# dwatch.net
KiCad netlist of a schematic drawn in Altium Designer
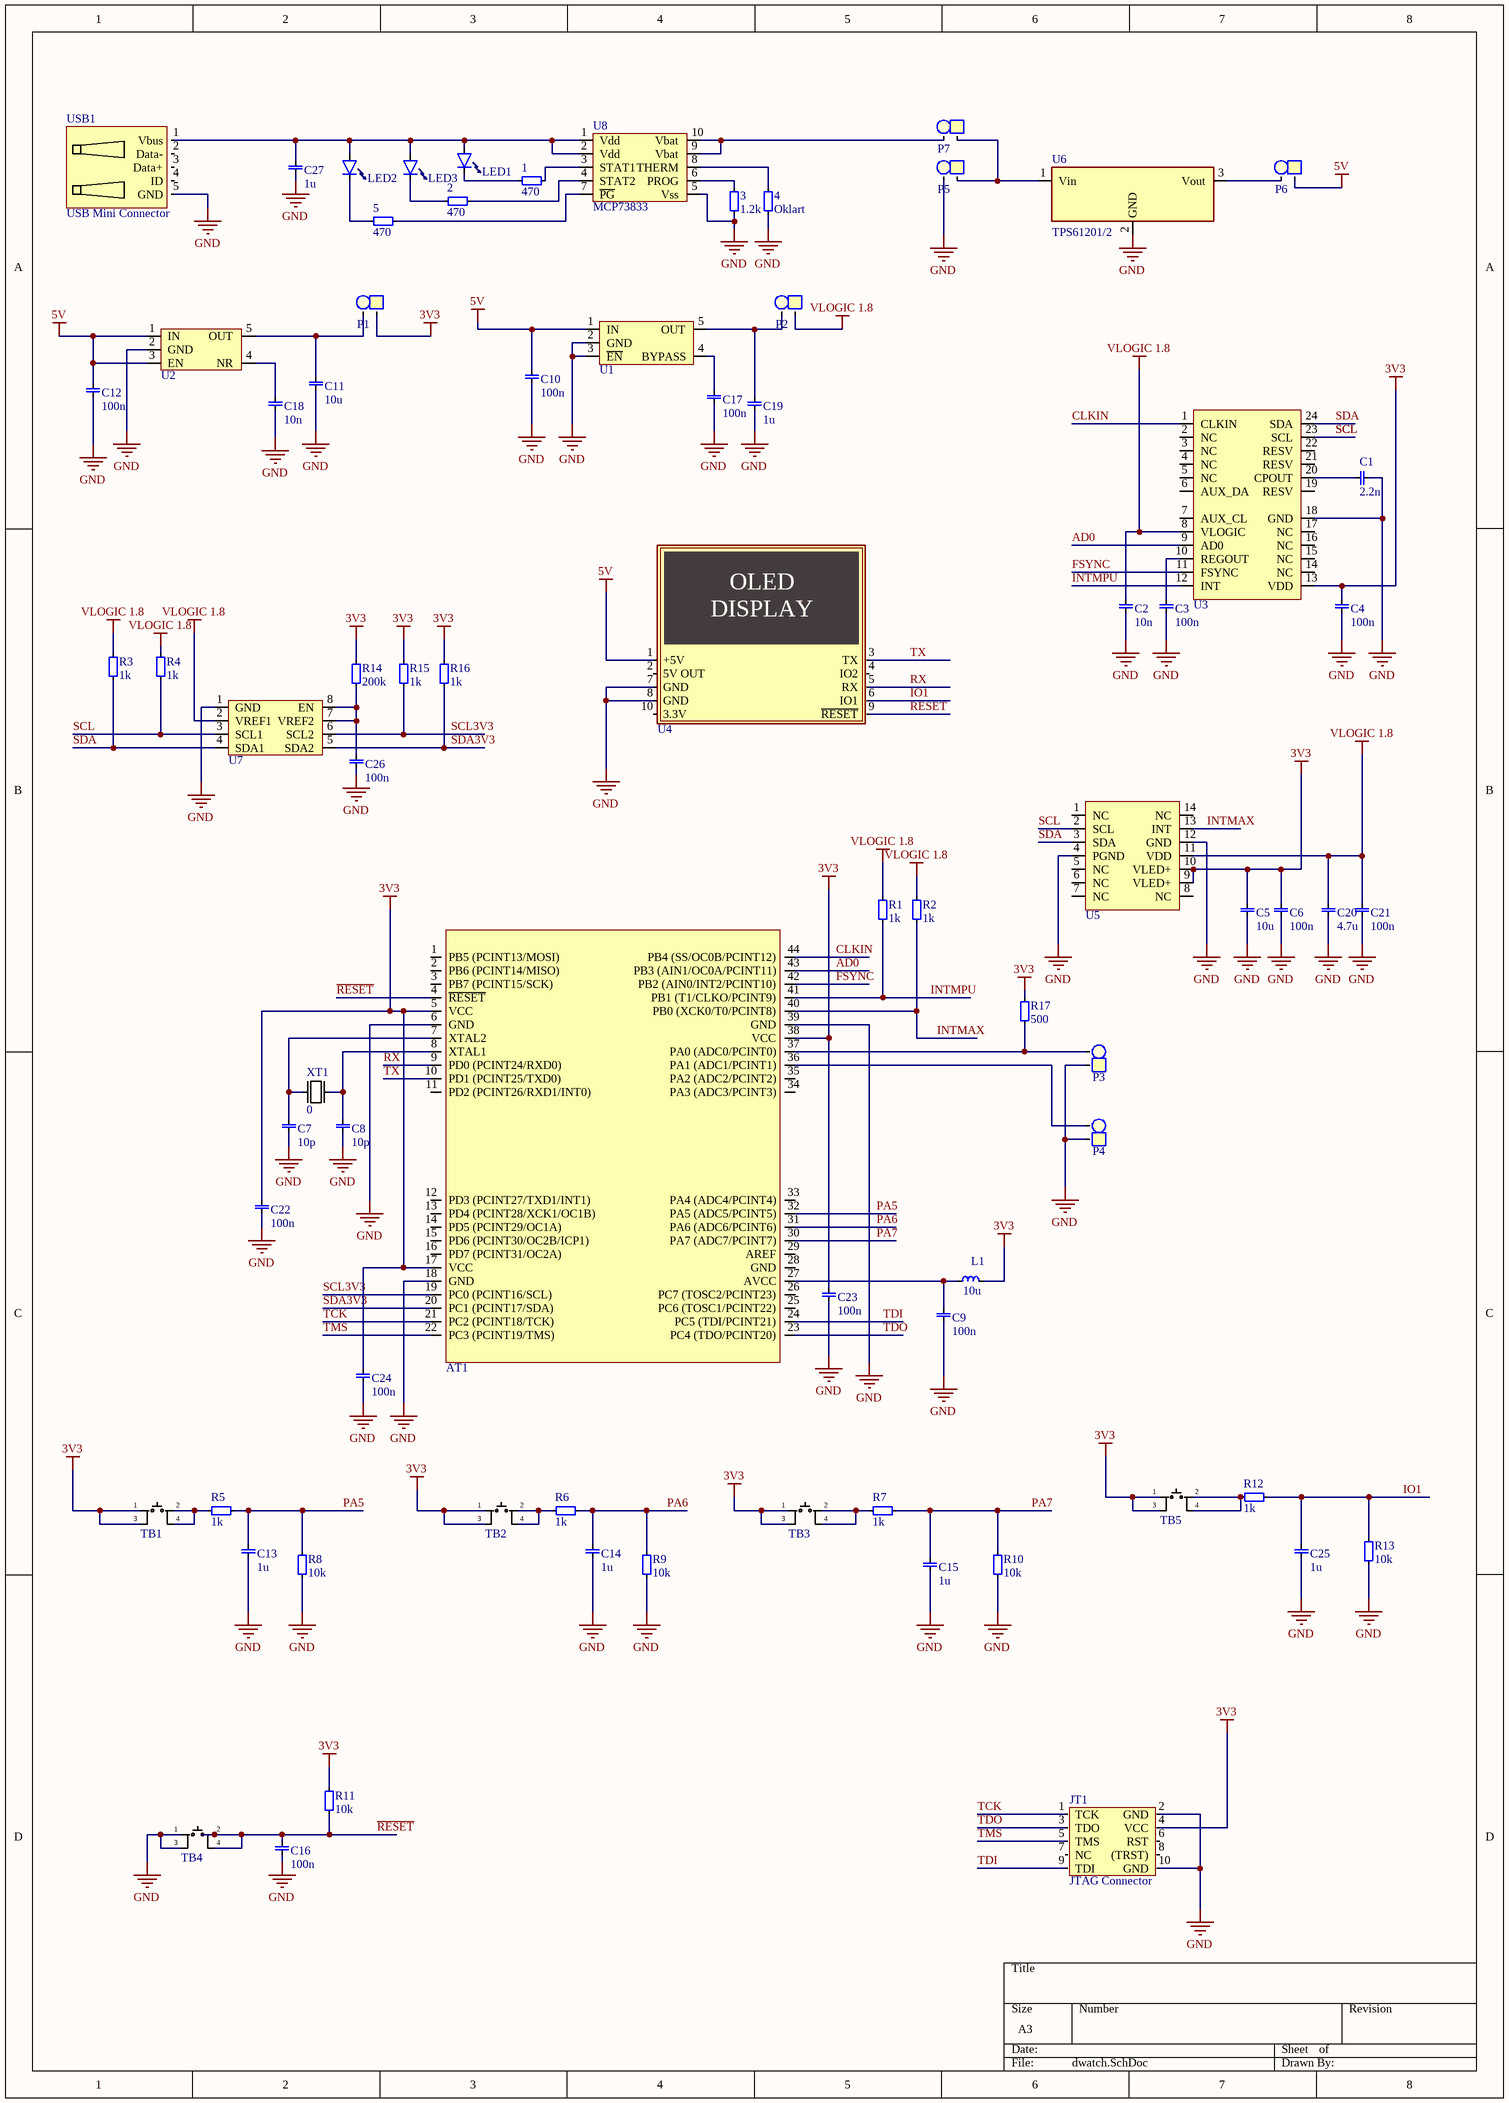
[diagram p0: dwatch.SchDoc]

(export (version "E")
  (design (tool "Eeschema 10.0.6"))
  (components
    (comp (ref "1")
      (value "470")
      (footprint "1206")
      (description "Resistor")
      (fields (field (name "Comment") "1206, resistor"))
      (libsource (lib "eitp15_lab1_lib") (part "1206, resistor"))
    )
    (comp (ref "2")
      (value "470")
      (footprint "1206")
      (description "Resistor")
      (fields (field (name "Comment") "1206, resistor"))
      (libsource (lib "eitp15_lab1_lib") (part "1206, resistor"))
    )
    (comp (ref "3")
      (value "1.2k")
      (footprint "1206")
      (description "Resistor")
      (fields (field (name "Comment") "1206, resistor"))
      (libsource (lib "eitp15_lab1_lib") (part "1206, resistor"))
    )
    (comp (ref "4")
      (value "Oklart")
      (footprint "1206")
      (description "Resistor")
      (fields (field (name "Comment") "1206, resistor"))
      (libsource (lib "eitp15_lab1_lib") (part "1206, resistor"))
    )
    (comp (ref "5")
      (value "470")
      (footprint "1206")
      (description "Resistor")
      (fields (field (name "Comment") "1206, resistor"))
      (libsource (lib "eitp15_lab1_lib") (part "1206, resistor"))
    )
    (comp (ref "AT1")
      (value "ATmega644PA")
      (footprint "TQFP-44")
      (description "ATmega644PA - Small but big and PicoPower")
      (libsource (lib "eitp15_lab1_lib") (part "ATmega644PA"))
    )
    (comp (ref "C1")
      (value "2.2n")
      (footprint "1206, capasitor")
      (fields (field (name "Comment") "1206, capacitor"))
      (libsource (lib "eitp15_lab1_lib") (part "1206, capacitor"))
    )
    (comp (ref "C2")
      (value "10n")
      (footprint "1206, capasitor")
      (fields (field (name "Comment") "1206, capacitor"))
      (libsource (lib "eitp15_lab1_lib") (part "1206, capacitor"))
    )
    (comp (ref "C3")
      (value "100n")
      (footprint "1206, capasitor")
      (fields (field (name "Comment") "1206, capacitor"))
      (libsource (lib "eitp15_lab1_lib") (part "1206, capacitor"))
    )
    (comp (ref "C4")
      (value "100n")
      (footprint "1206, capasitor")
      (fields (field (name "Comment") "1206, capacitor"))
      (libsource (lib "eitp15_lab1_lib") (part "1206, capacitor"))
    )
    (comp (ref "C5")
      (value "10u")
      (footprint "1206, capasitor")
      (fields (field (name "Comment") "1206, capacitor"))
      (libsource (lib "eitp15_lab1_lib") (part "1206, capacitor"))
    )
    (comp (ref "C6")
      (value "100n")
      (footprint "1206, capasitor")
      (fields (field (name "Comment") "1206, capacitor"))
      (libsource (lib "eitp15_lab1_lib") (part "1206, capacitor"))
    )
    (comp (ref "C7")
      (value "10p")
      (footprint "1206, capasitor")
      (fields (field (name "Comment") "1206, capacitor"))
      (libsource (lib "eitp15_lab1_lib") (part "1206, capacitor"))
    )
    (comp (ref "C8")
      (value "10p")
      (footprint "1206, capasitor")
      (fields (field (name "Comment") "1206, capacitor"))
      (libsource (lib "eitp15_lab1_lib") (part "1206, capacitor"))
    )
    (comp (ref "C9")
      (value "100n")
      (footprint "1206, capasitor")
      (fields (field (name "Comment") "1206, capacitor"))
      (libsource (lib "eitp15_lab1_lib") (part "1206, capacitor"))
    )
    (comp (ref "C10")
      (value "100n")
      (footprint "1206, capasitor")
      (fields (field (name "Comment") "1206, capacitor"))
      (libsource (lib "eitp15_lab1_lib") (part "1206, capacitor"))
    )
    (comp (ref "C11")
      (value "10u")
      (footprint "1206, capasitor")
      (fields (field (name "Comment") "1206, capacitor"))
      (libsource (lib "eitp15_lab1_lib") (part "1206, capacitor"))
    )
    (comp (ref "C12")
      (value "100n")
      (footprint "1206, capasitor")
      (fields (field (name "Comment") "1206, capacitor"))
      (libsource (lib "eitp15_lab1_lib") (part "1206, capacitor"))
    )
    (comp (ref "C13")
      (value "1u")
      (footprint "1206, capasitor")
      (fields (field (name "Comment") "1206, capacitor"))
      (libsource (lib "eitp15_lab1_lib") (part "1206, capacitor"))
    )
    (comp (ref "C14")
      (value "1u")
      (footprint "1206, capasitor")
      (fields (field (name "Comment") "1206, capacitor"))
      (libsource (lib "eitp15_lab1_lib") (part "1206, capacitor"))
    )
    (comp (ref "C15")
      (value "1u")
      (footprint "1206, capasitor")
      (fields (field (name "Comment") "1206, capacitor"))
      (libsource (lib "eitp15_lab1_lib") (part "1206, capacitor"))
    )
    (comp (ref "C16")
      (value "100n")
      (footprint "1206, capasitor")
      (fields (field (name "Comment") "1206, capacitor"))
      (libsource (lib "eitp15_lab1_lib") (part "1206, capacitor"))
    )
    (comp (ref "C17")
      (value "100n")
      (footprint "1206, capasitor")
      (fields (field (name "Comment") "1206, capacitor"))
      (libsource (lib "eitp15_lab1_lib") (part "1206, capacitor"))
    )
    (comp (ref "C18")
      (value "10n")
      (footprint "1206, capasitor")
      (fields (field (name "Comment") "1206, capacitor"))
      (libsource (lib "eitp15_lab1_lib") (part "1206, capacitor"))
    )
    (comp (ref "C19")
      (value "1u")
      (footprint "1206, capasitor")
      (fields (field (name "Comment") "1206, capacitor"))
      (libsource (lib "eitp15_lab1_lib") (part "1206, capacitor"))
    )
    (comp (ref "C20")
      (value "4.7u")
      (footprint "1206, capasitor")
      (fields (field (name "Comment") "1206, capacitor"))
      (libsource (lib "eitp15_lab1_lib") (part "1206, capacitor"))
    )
    (comp (ref "C21")
      (value "100n")
      (footprint "1206, capasitor")
      (fields (field (name "Comment") "1206, capacitor"))
      (libsource (lib "eitp15_lab1_lib") (part "1206, capacitor"))
    )
    (comp (ref "C22")
      (value "100n")
      (footprint "1206, capasitor")
      (fields (field (name "Comment") "1206, capacitor"))
      (libsource (lib "eitp15_lab1_lib") (part "1206, capacitor"))
    )
    (comp (ref "C23")
      (value "100n")
      (footprint "1206, capasitor")
      (fields (field (name "Comment") "1206, capacitor"))
      (libsource (lib "eitp15_lab1_lib") (part "1206, capacitor"))
    )
    (comp (ref "C24")
      (value "100n")
      (footprint "1206, capasitor")
      (fields (field (name "Comment") "1206, capacitor"))
      (libsource (lib "eitp15_lab1_lib") (part "1206, capacitor"))
    )
    (comp (ref "C25")
      (value "1u")
      (footprint "1206, capasitor")
      (fields (field (name "Comment") "1206, capacitor"))
      (libsource (lib "eitp15_lab1_lib") (part "1206, capacitor"))
    )
    (comp (ref "C26")
      (value "100n")
      (footprint "1206, capasitor")
      (fields (field (name "Comment") "1206, capacitor"))
      (libsource (lib "eitp15_lab1_lib") (part "1206, capacitor"))
    )
    (comp (ref "C27")
      (value "1u")
      (footprint "1206, capasitor")
      (fields (field (name "Comment") "1206, capacitor"))
      (libsource (lib "eitp15_lab1_lib") (part "1206, capacitor"))
    )
    (comp (ref "JT1")
      (value "JTAG Connector")
      (footprint "Atmel_JTAG")
      (description "Atmel JTAG Connector")
      (libsource (lib "eitp15_lab1_lib") (part "Atmel JTAG"))
    )
    (comp (ref "L1")
      (value "10u")
      (footprint "1812, coil")
      (fields (field (name "Comment") "Coil"))
      (libsource (lib "eitp15_lab1_lib") (part "Coil"))
    )
    (comp (ref "LED1")
      (value "0805, LED")
      (footprint "0805_led")
      (libsource (lib "eitp15_lab1_lib") (part "0805, LED"))
    )
    (comp (ref "LED2")
      (value "0805, LED")
      (footprint "0805_led")
      (libsource (lib "eitp15_lab1_lib") (part "0805, LED"))
    )
    (comp (ref "LED3")
      (value "0805, LED")
      (footprint "0805_led")
      (libsource (lib "eitp15_lab1_lib") (part "0805, LED"))
    )
    (comp (ref "P1")
      (value "1x2 Pin Header")
      (footprint "1x2HEADER")
      (description "2.54 mm, TH")
      (libsource (lib "") (part "1x2 Pin Header_1"))
    )
    (comp (ref "P2")
      (value "1x2 Pin Header")
      (footprint "1x2HEADER")
      (description "2.54 mm, TH")
      (libsource (lib "") (part "1x2 Pin Header_1"))
    )
    (comp (ref "P3")
      (value "1x2 Pin Header")
      (footprint "1x2HEADER")
      (description "2.54 mm, TH")
      (libsource (lib "eitp15_lab1_lib") (part "1x2 Pin Header"))
    )
    (comp (ref "P4")
      (value "1x2 Pin Header")
      (footprint "1x2HEADER")
      (description "2.54 mm, TH")
      (libsource (lib "eitp15_lab1_lib") (part "1x2 Pin Header"))
    )
    (comp (ref "P5")
      (value "1x2 Pin Header")
      (footprint "1x2HEADER")
      (description "2.54 mm, TH")
      (libsource (lib "") (part "1x2 Pin Header_1"))
    )
    (comp (ref "P6")
      (value "1x2 Pin Header")
      (footprint "1x2HEADER")
      (description "2.54 mm, TH")
      (libsource (lib "") (part "1x2 Pin Header_1"))
    )
    (comp (ref "P7")
      (value "1x2 Pin Header")
      (footprint "1x2HEADER")
      (description "2.54 mm, TH")
      (libsource (lib "") (part "1x2 Pin Header_1"))
    )
    (comp (ref "R1")
      (value "1k")
      (footprint "1206")
      (description "Resistor")
      (fields (field (name "Comment") "1206, resistor"))
      (libsource (lib "eitp15_lab1_lib") (part "1206, resistor"))
    )
    (comp (ref "R2")
      (value "1k")
      (footprint "1206")
      (description "Resistor")
      (fields (field (name "Comment") "1206, resistor"))
      (libsource (lib "eitp15_lab1_lib") (part "1206, resistor"))
    )
    (comp (ref "R3")
      (value "1k")
      (footprint "1206")
      (description "Resistor")
      (fields (field (name "Comment") "1206, resistor"))
      (libsource (lib "eitp15_lab1_lib") (part "1206, resistor"))
    )
    (comp (ref "R4")
      (value "1k")
      (footprint "1206")
      (description "Resistor")
      (fields (field (name "Comment") "1206, resistor"))
      (libsource (lib "eitp15_lab1_lib") (part "1206, resistor"))
    )
    (comp (ref "R5")
      (value "1k")
      (footprint "1206")
      (description "Resistor")
      (fields (field (name "Comment") "1206, resistor"))
      (libsource (lib "eitp15_lab1_lib") (part "1206, resistor"))
    )
    (comp (ref "R6")
      (value "1k")
      (footprint "1206")
      (description "Resistor")
      (fields (field (name "Comment") "1206, resistor"))
      (libsource (lib "eitp15_lab1_lib") (part "1206, resistor"))
    )
    (comp (ref "R7")
      (value "1k")
      (footprint "1206")
      (description "Resistor")
      (fields (field (name "Comment") "1206, resistor"))
      (libsource (lib "eitp15_lab1_lib") (part "1206, resistor"))
    )
    (comp (ref "R8")
      (value "10k")
      (footprint "1206")
      (description "Resistor")
      (fields (field (name "Comment") "1206, resistor"))
      (libsource (lib "eitp15_lab1_lib") (part "1206, resistor"))
    )
    (comp (ref "R9")
      (value "10k")
      (footprint "1206")
      (description "Resistor")
      (fields (field (name "Comment") "1206, resistor"))
      (libsource (lib "eitp15_lab1_lib") (part "1206, resistor"))
    )
    (comp (ref "R10")
      (value "10k")
      (footprint "1206")
      (description "Resistor")
      (fields (field (name "Comment") "1206, resistor"))
      (libsource (lib "eitp15_lab1_lib") (part "1206, resistor"))
    )
    (comp (ref "R11")
      (value "10k")
      (footprint "1206")
      (description "Resistor")
      (fields (field (name "Comment") "1206, resistor"))
      (libsource (lib "eitp15_lab1_lib") (part "1206, resistor"))
    )
    (comp (ref "R12")
      (value "1k")
      (footprint "1206")
      (description "Resistor")
      (fields (field (name "Comment") "1206, resistor"))
      (libsource (lib "eitp15_lab1_lib") (part "1206, resistor"))
    )
    (comp (ref "R13")
      (value "10k")
      (footprint "1206")
      (description "Resistor")
      (fields (field (name "Comment") "1206, resistor"))
      (libsource (lib "eitp15_lab1_lib") (part "1206, resistor"))
    )
    (comp (ref "R14")
      (value "200k")
      (footprint "1206")
      (description "Resistor")
      (fields (field (name "Comment") "1206, resistor"))
      (libsource (lib "eitp15_lab1_lib") (part "1206, resistor"))
    )
    (comp (ref "R15")
      (value "1k")
      (footprint "1206")
      (description "Resistor")
      (fields (field (name "Comment") "1206, resistor"))
      (libsource (lib "eitp15_lab1_lib") (part "1206, resistor"))
    )
    (comp (ref "R16")
      (value "1k")
      (footprint "1206")
      (description "Resistor")
      (fields (field (name "Comment") "1206, resistor"))
      (libsource (lib "eitp15_lab1_lib") (part "1206, resistor"))
    )
    (comp (ref "R17")
      (value "500")
      (footprint "1206")
      (description "Resistor")
      (fields (field (name "Comment") "1206, resistor"))
      (libsource (lib "eitp15_lab1_lib") (part "1206, resistor"))
    )
    (comp (ref "TB1")
      (value "Tactile Button")
      (footprint "Button smd")
      (description "Tactile Switch Small Low")
      (libsource (lib "eitp15_lab1_lib") (part "Button SMD"))
    )
    (comp (ref "TB2")
      (value "Tactile Button")
      (footprint "Button smd")
      (description "Tactile Switch Small Low")
      (libsource (lib "eitp15_lab1_lib") (part "Button SMD"))
    )
    (comp (ref "TB3")
      (value "Tactile Button")
      (footprint "Button smd")
      (description "Tactile Switch Small Low")
      (libsource (lib "eitp15_lab1_lib") (part "Button SMD"))
    )
    (comp (ref "TB4")
      (value "Tactile Button")
      (footprint "Button smd")
      (description "Tactile Switch Small Low")
      (libsource (lib "eitp15_lab1_lib") (part "Button SMD"))
    )
    (comp (ref "TB5")
      (value "Tactile Button")
      (footprint "Button smd")
      (description "Tactile Switch Small Low")
      (libsource (lib "eitp15_lab1_lib") (part "Button SMD"))
    )
    (comp (ref "U1")
      (value "TPS79118DBVR")
      (footprint "SOT23-5")
      (libsource (lib "dwatch") (part "TPS79118DBVR"))
    )
    (comp (ref "U2")
      (value "TPS79333DBVRG4")
      (footprint "SOT23-5")
      (libsource (lib "dwatch") (part "TPS79333DBVRG4"))
    )
    (comp (ref "U3")
      (value "MPU-6050")
      (footprint "MPU6050_QNF24")
      (libsource (lib "dwatch") (part "MPU-6050"))
    )
    (comp (ref "U4")
      (value "uOLED-128G2")
      (footprint "uOLED-128G2")
      (libsource (lib "jclib") (part "uOLED-128G2"))
    )
    (comp (ref "U5")
      (value "MAX30101")
      (footprint "MAX30101EFD")
      (libsource (lib "dwatch") (part "MAX30101"))
    )
    (comp (ref "U6")
      (value "TPS61201/2")
      (footprint "tps61201_2")
      (libsource (lib "tps61201_2_lib") (part "TPS61201/2"))
    )
    (comp (ref "U7") (value "PCA9306") (footprint "PCA9306") (libsource (lib "dwatch") (part "PCA9306")))
    (comp (ref "U8") (value "MCP73833") (footprint "MCP73833") (libsource (lib "dwatch") (part "MCP73833")))
    (comp (ref "USB1")
      (value "USB Mini Connector")
      (footprint "USB Mini TH")
      (libsource (lib "jclib") (part "USB Mini Connector"))
    )
    (comp (ref "XT1")
      (value "0")
      (footprint "XTAL_SMD_LP")
      (description "16 MHz, SMD, 5mm x 3,2mm, 30 ppm")
      (fields (field (name "Comment") "XTAL TXC 7A"))
      (libsource (lib "eitp15_lab1_lib") (part "XTAL TXC 7A"))
    )
  )
  (nets
    (net (code "1") (name "/AD0") (class "Default")
      (node (ref "AT1") (pin "43") (pinfunction "PB3_(AIN1/OC0A/PCINT11)_43") (pintype "passive"))
      (node (ref "U3") (pin "9") (pinfunction "AD0_9") (pintype "passive"))
    )
    (net (code "2") (name "/CLKIN") (class "Default")
      (node (ref "AT1") (pin "44") (pinfunction "PB4_(SS/OC0B/PCINT12)_44") (pintype "passive"))
      (node (ref "U3") (pin "1") (pinfunction "CLKIN_1") (pintype "passive"))
    )
    (net (code "3") (name "/FSYNC") (class "Default")
      (node (ref "AT1") (pin "42") (pinfunction "PB2_(AIN0/INT2/PCINT10)_42") (pintype "passive"))
      (node (ref "U3") (pin "11") (pinfunction "FSYNC_11") (pintype "passive"))
    )
    (net (code "4") (name "/INTMAX") (class "Default")
      (node (ref "AT1") (pin "40") (pinfunction "PB0_(XCK0/T0/PCINT8)_40") (pintype "passive"))
      (node (ref "R2") (pin "1") (pinfunction "1_1") (pintype "passive"))
      (node (ref "U5") (pin "13") (pinfunction "INT_13") (pintype "passive"))
    )
    (net (code "5") (name "/INTMPU") (class "Default")
      (node (ref "AT1") (pin "41") (pinfunction "PB1_(T1/CLKO/PCINT9)_41") (pintype "passive"))
      (node (ref "R1") (pin "1") (pinfunction "1_1") (pintype "passive"))
      (node (ref "U3") (pin "12") (pinfunction "INT_12") (pintype "passive"))
    )
    (net (code "6") (name "/IO1") (class "Default")
      (node (ref "C25") (pin "1") (pinfunction "1_1") (pintype "passive"))
      (node (ref "R12") (pin "0") (pinfunction "0_0") (pintype "passive"))
      (node (ref "R13") (pin "0") (pinfunction "0_0") (pintype "passive"))
      (node (ref "U4") (pin "6") (pinfunction "IO1_6") (pintype "passive"))
    )
    (net (code "7") (name "/PA5") (class "Default")
      (node (ref "AT1") (pin "32") (pinfunction "PA5_(ADC5/PCINT5)_32") (pintype "passive"))
      (node (ref "C13") (pin "1") (pinfunction "1_1") (pintype "passive"))
      (node (ref "R5") (pin "0") (pinfunction "0_0") (pintype "passive"))
      (node (ref "R8") (pin "0") (pinfunction "0_0") (pintype "passive"))
    )
    (net (code "8") (name "/PA6") (class "Default")
      (node (ref "AT1") (pin "31") (pinfunction "PA6_(ADC6/PCINT6)_31") (pintype "passive"))
      (node (ref "C14") (pin "1") (pinfunction "1_1") (pintype "passive"))
      (node (ref "R6") (pin "0") (pinfunction "0_0") (pintype "passive"))
      (node (ref "R9") (pin "0") (pinfunction "0_0") (pintype "passive"))
    )
    (net (code "9") (name "/PA7") (class "Default")
      (node (ref "AT1") (pin "30") (pinfunction "PA7_(ADC7/PCINT7)_30") (pintype "passive"))
      (node (ref "C15") (pin "1") (pinfunction "1_1") (pintype "passive"))
      (node (ref "R10") (pin "0") (pinfunction "0_0") (pintype "passive"))
      (node (ref "R7") (pin "0") (pinfunction "0_0") (pintype "passive"))
    )
    (net (code "10") (name "/RX") (class "Default")
      (node (ref "AT1") (pin "9") (pinfunction "PD0_(PCINT24/RXD0)_9") (pintype "passive"))
      (node (ref "U4") (pin "5") (pinfunction "RX_5") (pintype "passive"))
    )
    (net (code "11") (name "/SCL") (class "Default")
      (node (ref "R4") (pin "1") (pinfunction "1_1") (pintype "passive"))
      (node (ref "U3") (pin "23") (pinfunction "SCL_23") (pintype "passive"))
      (node (ref "U5") (pin "2") (pinfunction "SCL_2") (pintype "passive"))
      (node (ref "U7") (pin "3") (pinfunction "SCL1_3") (pintype "passive"))
    )
    (net (code "12") (name "/SCL3V3") (class "Default")
      (node (ref "AT1") (pin "19") (pinfunction "PC0_(PCINT16/SCL)_19") (pintype "passive"))
      (node (ref "R15") (pin "1") (pinfunction "1_1") (pintype "passive"))
      (node (ref "U7") (pin "6") (pinfunction "SCL2_6") (pintype "passive"))
    )
    (net (code "13") (name "/SDA") (class "Default")
      (node (ref "R3") (pin "1") (pinfunction "1_1") (pintype "passive"))
      (node (ref "U3") (pin "24") (pinfunction "SDA_24") (pintype "passive"))
      (node (ref "U5") (pin "3") (pinfunction "SDA_3") (pintype "passive"))
      (node (ref "U7") (pin "4") (pinfunction "SDA1_4") (pintype "passive"))
    )
    (net (code "14") (name "/SDA3V3") (class "Default")
      (node (ref "AT1") (pin "20") (pinfunction "PC1_(PCINT17/SDA)_20") (pintype "passive"))
      (node (ref "R16") (pin "1") (pinfunction "1_1") (pintype "passive"))
      (node (ref "U7") (pin "5") (pinfunction "SDA2_5") (pintype "passive"))
    )
    (net (code "15") (name "/TCK") (class "Default")
      (node (ref "AT1") (pin "21") (pinfunction "PC2_(PCINT18/TCK)_21") (pintype "passive"))
      (node (ref "JT1") (pin "1") (pinfunction "TCK_1") (pintype "passive"))
    )
    (net (code "16") (name "/TDI") (class "Default")
      (node (ref "AT1") (pin "24") (pinfunction "PC5_(TDI/PCINT21)_24") (pintype "passive"))
      (node (ref "JT1") (pin "9") (pinfunction "TDI_9") (pintype "passive"))
    )
    (net (code "17") (name "/TDO") (class "Default")
      (node (ref "AT1") (pin "23") (pinfunction "PC4_(TDO/PCINT20)_23") (pintype "passive"))
      (node (ref "JT1") (pin "3") (pinfunction "TDO_3") (pintype "passive"))
    )
    (net (code "18") (name "/TMS") (class "Default")
      (node (ref "AT1") (pin "22") (pinfunction "PC3_(PCINT19/TMS)_22") (pintype "passive"))
      (node (ref "JT1") (pin "5") (pinfunction "TMS_5") (pintype "passive"))
    )
    (net (code "19") (name "/TX") (class "Default")
      (node (ref "AT1") (pin "10") (pinfunction "PD1_(PCINT25/TXD0)_10") (pintype "passive"))
      (node (ref "U4") (pin "3") (pinfunction "TX_3") (pintype "passive"))
    )
    (net (code "20") (name "/~{RESET}") (class "Default")
      (node (ref "AT1") (pin "4") (pinfunction "~{RESET}_4") (pintype "passive"))
      (node (ref "C16") (pin "1") (pinfunction "1_1") (pintype "passive"))
      (node (ref "R11") (pin "1") (pinfunction "1_1") (pintype "passive"))
      (node (ref "TB4") (pin "2") (pinfunction "2_2") (pintype "passive"))
      (node (ref "TB4") (pin "4") (pinfunction "4_4") (pintype "passive"))
      (node (ref "U4") (pin "9") (pinfunction "~{RESET}_9") (pintype "passive"))
    )
    (net (code "21") (name "3V3") (class "Default")
      (node (ref "AT1") (pin "17") (pinfunction "VCC_17") (pintype "passive"))
      (node (ref "AT1") (pin "38") (pinfunction "VCC_38") (pintype "passive"))
      (node (ref "AT1") (pin "5") (pinfunction "VCC_5") (pintype "passive"))
      (node (ref "C22") (pin "1") (pinfunction "1_1") (pintype "passive"))
      (node (ref "C23") (pin "1") (pinfunction "1_1") (pintype "passive"))
      (node (ref "C24") (pin "1") (pinfunction "1_1") (pintype "passive"))
      (node (ref "C4") (pin "1") (pinfunction "1_1") (pintype "passive"))
      (node (ref "C5") (pin "1") (pinfunction "1_1") (pintype "passive"))
      (node (ref "C6") (pin "1") (pinfunction "1_1") (pintype "passive"))
      (node (ref "JT1") (pin "4") (pinfunction "VCC_4") (pintype "passive"))
      (node (ref "L1") (pin "1") (pinfunction "1_1") (pintype "passive"))
      (node (ref "P1") (pin "1") (pinfunction "1_1") (pintype "passive"))
      (node (ref "R11") (pin "0") (pinfunction "0_0") (pintype "passive"))
      (node (ref "R14") (pin "0") (pinfunction "0_0") (pintype "passive"))
      (node (ref "R15") (pin "0") (pinfunction "0_0") (pintype "passive"))
      (node (ref "R16") (pin "0") (pinfunction "0_0") (pintype "passive"))
      (node (ref "R17") (pin "0") (pinfunction "0_0") (pintype "passive"))
      (node (ref "TB1") (pin "1") (pinfunction "1_1") (pintype "passive"))
      (node (ref "TB1") (pin "3") (pinfunction "3_3") (pintype "passive"))
      (node (ref "TB2") (pin "1") (pinfunction "1_1") (pintype "passive"))
      (node (ref "TB2") (pin "3") (pinfunction "3_3") (pintype "passive"))
      (node (ref "TB3") (pin "1") (pinfunction "1_1") (pintype "passive"))
      (node (ref "TB3") (pin "3") (pinfunction "3_3") (pintype "passive"))
      (node (ref "TB5") (pin "1") (pinfunction "1_1") (pintype "passive"))
      (node (ref "TB5") (pin "3") (pinfunction "3_3") (pintype "passive"))
      (node (ref "U3") (pin "13") (pinfunction "VDD_13") (pintype "passive"))
      (node (ref "U5") (pin "10") (pinfunction "VLED+_10") (pintype "passive"))
      (node (ref "U5") (pin "9") (pinfunction "VLED+_9") (pintype "passive"))
    )
    (net (code "22") (name "5V") (class "Default")
      (node (ref "C10") (pin "1") (pinfunction "1_1") (pintype "passive"))
      (node (ref "C12") (pin "1") (pinfunction "1_1") (pintype "passive"))
      (node (ref "P6") (pin "1") (pinfunction "1_1") (pintype "passive"))
      (node (ref "U1") (pin "1") (pinfunction "IN_1") (pintype "passive"))
      (node (ref "U2") (pin "1") (pinfunction "IN_1") (pintype "passive"))
      (node (ref "U2") (pin "3") (pinfunction "EN_3") (pintype "passive"))
      (node (ref "U4") (pin "1") (pinfunction "+5V_1") (pintype "passive"))
    )
    (net (code "23") (name "GND") (class "Default")
      (node (ref "3") (pin "1") (pinfunction "1_1") (pintype "passive"))
      (node (ref "4") (pin "1") (pinfunction "1_1") (pintype "passive"))
      (node (ref "AT1") (pin "18") (pinfunction "GND_18") (pintype "passive"))
      (node (ref "AT1") (pin "39") (pinfunction "GND_39") (pintype "passive"))
      (node (ref "AT1") (pin "6") (pinfunction "GND_6") (pintype "passive"))
      (node (ref "C1") (pin "1") (pinfunction "1_1") (pintype "passive"))
      (node (ref "C10") (pin "0") (pinfunction "0_0") (pintype "passive"))
      (node (ref "C11") (pin "0") (pinfunction "0_0") (pintype "passive"))
      (node (ref "C12") (pin "0") (pinfunction "0_0") (pintype "passive"))
      (node (ref "C13") (pin "0") (pinfunction "0_0") (pintype "passive"))
      (node (ref "C14") (pin "0") (pinfunction "0_0") (pintype "passive"))
      (node (ref "C15") (pin "0") (pinfunction "0_0") (pintype "passive"))
      (node (ref "C16") (pin "0") (pinfunction "0_0") (pintype "passive"))
      (node (ref "C17") (pin "0") (pinfunction "0_0") (pintype "passive"))
      (node (ref "C18") (pin "0") (pinfunction "0_0") (pintype "passive"))
      (node (ref "C19") (pin "0") (pinfunction "0_0") (pintype "passive"))
      (node (ref "C2") (pin "0") (pinfunction "0_0") (pintype "passive"))
      (node (ref "C20") (pin "0") (pinfunction "0_0") (pintype "passive"))
      (node (ref "C21") (pin "0") (pinfunction "0_0") (pintype "passive"))
      (node (ref "C22") (pin "0") (pinfunction "0_0") (pintype "passive"))
      (node (ref "C23") (pin "0") (pinfunction "0_0") (pintype "passive"))
      (node (ref "C24") (pin "0") (pinfunction "0_0") (pintype "passive"))
      (node (ref "C25") (pin "0") (pinfunction "0_0") (pintype "passive"))
      (node (ref "C26") (pin "0") (pinfunction "0_0") (pintype "passive"))
      (node (ref "C27") (pin "0") (pinfunction "0_0") (pintype "passive"))
      (node (ref "C3") (pin "0") (pinfunction "0_0") (pintype "passive"))
      (node (ref "C4") (pin "0") (pinfunction "0_0") (pintype "passive"))
      (node (ref "C5") (pin "0") (pinfunction "0_0") (pintype "passive"))
      (node (ref "C6") (pin "0") (pinfunction "0_0") (pintype "passive"))
      (node (ref "C7") (pin "0") (pinfunction "0_0") (pintype "passive"))
      (node (ref "C8") (pin "0") (pinfunction "0_0") (pintype "passive"))
      (node (ref "C9") (pin "0") (pinfunction "0_0") (pintype "passive"))
      (node (ref "JT1") (pin "10") (pinfunction "GND_10") (pintype "passive"))
      (node (ref "JT1") (pin "2") (pinfunction "GND_2") (pintype "passive"))
      (node (ref "P3") (pin "1") (pinfunction "1_1") (pintype "passive"))
      (node (ref "P4") (pin "1") (pinfunction "1_1") (pintype "passive"))
      (node (ref "P5") (pin "2") (pinfunction "2_2") (pintype "passive"))
      (node (ref "R10") (pin "1") (pinfunction "1_1") (pintype "passive"))
      (node (ref "R13") (pin "1") (pinfunction "1_1") (pintype "passive"))
      (node (ref "R8") (pin "1") (pinfunction "1_1") (pintype "passive"))
      (node (ref "R9") (pin "1") (pinfunction "1_1") (pintype "passive"))
      (node (ref "TB4") (pin "1") (pinfunction "1_1") (pintype "passive"))
      (node (ref "TB4") (pin "3") (pinfunction "3_3") (pintype "passive"))
      (node (ref "U1") (pin "2") (pinfunction "GND_2") (pintype "passive"))
      (node (ref "U1") (pin "3") (pinfunction "~{EN}_3") (pintype "passive"))
      (node (ref "U2") (pin "2") (pinfunction "GND_2") (pintype "passive"))
      (node (ref "U3") (pin "18") (pinfunction "GND_18") (pintype "passive"))
      (node (ref "U4") (pin "7") (pinfunction "GND_7") (pintype "passive"))
      (node (ref "U4") (pin "8") (pinfunction "GND_8") (pintype "passive"))
      (node (ref "U5") (pin "12") (pinfunction "GND_12") (pintype "passive"))
      (node (ref "U5") (pin "4") (pinfunction "PGND_4") (pintype "passive"))
      (node (ref "U6") (pin "2") (pinfunction "GND_2") (pintype "passive"))
      (node (ref "U7") (pin "1") (pinfunction "GND_1") (pintype "passive"))
      (node (ref "U8") (pin "5") (pinfunction "Vss_5") (pintype "passive"))
      (node (ref "USB1") (pin "5") (pinfunction "GND_5") (pintype "passive"))
    )
    (net (code "24") (name "Net-(AT1-AVCC)") (class "Default")
      (node (ref "AT1") (pin "27") (pinfunction "AVCC_27") (pintype "passive"))
      (node (ref "C9") (pin "1") (pinfunction "1_1") (pintype "passive"))
      (node (ref "L1") (pin "2") (pinfunction "2_2") (pintype "passive"))
    )
    (net (code "25") (name "Net-(AT1-PA0_(ADC0{slash}PCINT0))") (class "Default")
      (node (ref "AT1") (pin "37") (pinfunction "PA0_(ADC0/PCINT0)_37") (pintype "passive"))
      (node (ref "P3") (pin "2") (pinfunction "2_2") (pintype "passive"))
      (node (ref "R17") (pin "1") (pinfunction "1_1") (pintype "passive"))
    )
    (net (code "26") (name "Net-(AT1-PA1_(ADC1{slash}PCINT1))") (class "Default")
      (node (ref "AT1") (pin "36") (pinfunction "PA1_(ADC1/PCINT1)_36") (pintype "passive"))
      (node (ref "P4") (pin "2") (pinfunction "2_2") (pintype "passive"))
    )
    (net (code "27") (name "Net-(AT1-XTAL1)") (class "Default")
      (node (ref "AT1") (pin "8") (pinfunction "XTAL1_8") (pintype "passive"))
      (node (ref "C8") (pin "1") (pinfunction "1_1") (pintype "passive"))
      (node (ref "XT1") (pin "2") (pinfunction "2_2") (pintype "passive"))
    )
    (net (code "28") (name "Net-(AT1-XTAL2)") (class "Default")
      (node (ref "AT1") (pin "7") (pinfunction "XTAL2_7") (pintype "passive"))
      (node (ref "C7") (pin "1") (pinfunction "1_1") (pintype "passive"))
      (node (ref "XT1") (pin "1") (pinfunction "1_1") (pintype "passive"))
    )
    (net (code "29") (name "Net-(LED1-Cathode)") (class "Default")
      (node (ref "1") (pin "1") (pinfunction "1_1") (pintype "passive"))
      (node (ref "LED1") (pin "0") (pinfunction "Cathode_0") (pintype "passive"))
    )
    (net (code "30") (name "Net-(LED2-Cathode)") (class "Default")
      (node (ref "5") (pin "1") (pinfunction "1_1") (pintype "passive"))
      (node (ref "LED2") (pin "0") (pinfunction "Cathode_0") (pintype "passive"))
    )
    (net (code "31") (name "Net-(LED3-Cathode)") (class "Default")
      (node (ref "2") (pin "1") (pinfunction "1_1") (pintype "passive"))
      (node (ref "LED3") (pin "0") (pinfunction "Cathode_0") (pintype "passive"))
    )
    (net (code "32") (name "Net-(P7-Pad2)") (class "Default")
      (node (ref "P7") (pin "2") (pinfunction "2_2") (pintype "passive"))
      (node (ref "U8") (pin "10") (pinfunction "Vbat_10") (pintype "passive"))
      (node (ref "U8") (pin "9") (pinfunction "Vbat_9") (pintype "passive"))
    )
    (net (code "33") (name "Net-(R5-Pad1)") (class "Default")
      (node (ref "R5") (pin "1") (pinfunction "1_1") (pintype "passive"))
      (node (ref "TB1") (pin "2") (pinfunction "2_2") (pintype "passive"))
      (node (ref "TB1") (pin "4") (pinfunction "4_4") (pintype "passive"))
    )
    (net (code "34") (name "Net-(R6-Pad1)") (class "Default")
      (node (ref "R6") (pin "1") (pinfunction "1_1") (pintype "passive"))
      (node (ref "TB2") (pin "2") (pinfunction "2_2") (pintype "passive"))
      (node (ref "TB2") (pin "4") (pinfunction "4_4") (pintype "passive"))
    )
    (net (code "35") (name "Net-(R7-Pad1)") (class "Default")
      (node (ref "R7") (pin "1") (pinfunction "1_1") (pintype "passive"))
      (node (ref "TB3") (pin "2") (pinfunction "2_2") (pintype "passive"))
      (node (ref "TB3") (pin "4") (pinfunction "4_4") (pintype "passive"))
    )
    (net (code "36") (name "Net-(R12-Pad1)") (class "Default")
      (node (ref "R12") (pin "1") (pinfunction "1_1") (pintype "passive"))
      (node (ref "TB5") (pin "2") (pinfunction "2_2") (pintype "passive"))
      (node (ref "TB5") (pin "4") (pinfunction "4_4") (pintype "passive"))
    )
    (net (code "37") (name "Net-(U1-BYPASS)") (class "Default")
      (node (ref "C17") (pin "1") (pinfunction "1_1") (pintype "passive"))
      (node (ref "U1") (pin "4") (pinfunction "BYPASS_4") (pintype "passive"))
    )
    (net (code "38") (name "Net-(U1-OUT)") (class "Default")
      (node (ref "C19") (pin "1") (pinfunction "1_1") (pintype "passive"))
      (node (ref "P2") (pin "2") (pinfunction "2_2") (pintype "passive"))
      (node (ref "U1") (pin "5") (pinfunction "OUT_5") (pintype "passive"))
    )
    (net (code "39") (name "Net-(U2-NR)") (class "Default")
      (node (ref "C18") (pin "1") (pinfunction "1_1") (pintype "passive"))
      (node (ref "U2") (pin "4") (pinfunction "NR_4") (pintype "passive"))
    )
    (net (code "40") (name "Net-(U2-OUT)") (class "Default")
      (node (ref "C11") (pin "1") (pinfunction "1_1") (pintype "passive"))
      (node (ref "P1") (pin "2") (pinfunction "2_2") (pintype "passive"))
      (node (ref "U2") (pin "5") (pinfunction "OUT_5") (pintype "passive"))
    )
    (net (code "41") (name "Net-(U3-CPOUT)") (class "Default")
      (node (ref "C1") (pin "0") (pinfunction "0_0") (pintype "passive"))
      (node (ref "U3") (pin "20") (pinfunction "CPOUT_20") (pintype "passive"))
    )
    (net (code "42") (name "Net-(U3-REGOUT)") (class "Default")
      (node (ref "C3") (pin "1") (pinfunction "1_1") (pintype "passive"))
      (node (ref "U3") (pin "10") (pinfunction "REGOUT_10") (pintype "passive"))
    )
    (net (code "43") (name "Net-(U6-Vin)") (class "Default")
      (node (ref "P5") (pin "1") (pinfunction "1_1") (pintype "passive"))
      (node (ref "P7") (pin "1") (pinfunction "1_1") (pintype "passive"))
      (node (ref "U6") (pin "1") (pinfunction "Vin_1") (pintype "passive"))
    )
    (net (code "44") (name "Net-(U6-Vout)") (class "Default")
      (node (ref "P6") (pin "2") (pinfunction "2_2") (pintype "passive"))
      (node (ref "U6") (pin "3") (pinfunction "Vout_3") (pintype "passive"))
    )
    (net (code "45") (name "Net-(U7-EN)") (class "Default")
      (node (ref "C26") (pin "1") (pinfunction "1_1") (pintype "passive"))
      (node (ref "R14") (pin "1") (pinfunction "1_1") (pintype "passive"))
      (node (ref "U7") (pin "7") (pinfunction "VREF2_7") (pintype "passive"))
      (node (ref "U7") (pin "8") (pinfunction "EN_8") (pintype "passive"))
    )
    (net (code "46") (name "Net-(U8-PROG)") (class "Default")
      (node (ref "3") (pin "0") (pinfunction "0_0") (pintype "passive"))
      (node (ref "U8") (pin "6") (pinfunction "PROG_6") (pintype "passive"))
    )
    (net (code "47") (name "Net-(U8-STAT1)") (class "Default")
      (node (ref "1") (pin "0") (pinfunction "0_0") (pintype "passive"))
      (node (ref "U8") (pin "3") (pinfunction "STAT1_3") (pintype "passive"))
    )
    (net (code "48") (name "Net-(U8-STAT2)") (class "Default")
      (node (ref "2") (pin "0") (pinfunction "0_0") (pintype "passive"))
      (node (ref "U8") (pin "4") (pinfunction "STAT2_4") (pintype "passive"))
    )
    (net (code "49") (name "Net-(U8-THERM)") (class "Default")
      (node (ref "4") (pin "0") (pinfunction "0_0") (pintype "passive"))
      (node (ref "U8") (pin "8") (pinfunction "THERM_8") (pintype "passive"))
    )
    (net (code "50") (name "Net-(U8-~{PG})") (class "Default")
      (node (ref "5") (pin "0") (pinfunction "0_0") (pintype "passive"))
      (node (ref "U8") (pin "7") (pinfunction "~{PG}_7") (pintype "passive"))
    )
    (net (code "51") (name "Net-(USB1-Vbus)") (class "Default")
      (node (ref "C27") (pin "1") (pinfunction "1_1") (pintype "passive"))
      (node (ref "LED1") (pin "1") (pinfunction "1_1") (pintype "passive"))
      (node (ref "LED2") (pin "1") (pinfunction "1_1") (pintype "passive"))
      (node (ref "LED3") (pin "1") (pinfunction "1_1") (pintype "passive"))
      (node (ref "U8") (pin "1") (pinfunction "Vdd_1") (pintype "passive"))
      (node (ref "U8") (pin "2") (pinfunction "Vdd_2") (pintype "passive"))
      (node (ref "USB1") (pin "1") (pinfunction "Vbus_1") (pintype "passive"))
    )
    (net (code "52") (name "VLOGIC 1.8") (class "Default")
      (node (ref "C2") (pin "1") (pinfunction "1_1") (pintype "passive"))
      (node (ref "C20") (pin "1") (pinfunction "1_1") (pintype "passive"))
      (node (ref "C21") (pin "1") (pinfunction "1_1") (pintype "passive"))
      (node (ref "P2") (pin "1") (pinfunction "1_1") (pintype "passive"))
      (node (ref "R1") (pin "0") (pinfunction "0_0") (pintype "passive"))
      (node (ref "R2") (pin "0") (pinfunction "0_0") (pintype "passive"))
      (node (ref "R3") (pin "0") (pinfunction "0_0") (pintype "passive"))
      (node (ref "R4") (pin "0") (pinfunction "0_0") (pintype "passive"))
      (node (ref "U3") (pin "8") (pinfunction "VLOGIC_8") (pintype "passive"))
      (node (ref "U5") (pin "11") (pinfunction "VDD_11") (pintype "passive"))
      (node (ref "U7") (pin "2") (pinfunction "VREF1_2") (pintype "passive"))
    )
    (net (code "53") (name "unconnected-(AT1-AREF-Pad29)") (class "Default")
      (node (ref "AT1") (pin "29") (pinfunction "AREF_29") (pintype "passive"))
    )
    (net (code "54") (name "unconnected-(AT1-GND-Pad28)") (class "Default")
      (node (ref "AT1") (pin "28") (pinfunction "GND_28") (pintype "passive"))
    )
    (net (code "55") (name "unconnected-(AT1-PA2_(ADC2{slash}PCINT2)-Pad35)") (class "Default")
      (node (ref "AT1") (pin "35") (pinfunction "PA2_(ADC2/PCINT2)_35") (pintype "passive"))
    )
    (net (code "56") (name "unconnected-(AT1-PA3_(ADC3{slash}PCINT3)-Pad34)") (class "Default")
      (node (ref "AT1") (pin "34") (pinfunction "PA3_(ADC3/PCINT3)_34") (pintype "passive"))
    )
    (net (code "57") (name "unconnected-(AT1-PA4_(ADC4{slash}PCINT4)-Pad33)") (class "Default")
      (node (ref "AT1") (pin "33") (pinfunction "PA4_(ADC4/PCINT4)_33") (pintype "passive"))
    )
    (net (code "58") (name "unconnected-(AT1-PB5_(PCINT13{slash}MOSI)-Pad1)") (class "Default")
      (node (ref "AT1") (pin "1") (pinfunction "PB5_(PCINT13/MOSI)_1") (pintype "passive"))
    )
    (net (code "59") (name "unconnected-(AT1-PB6_(PCINT14{slash}MISO)-Pad2)") (class "Default")
      (node (ref "AT1") (pin "2") (pinfunction "PB6_(PCINT14/MISO)_2") (pintype "passive"))
    )
    (net (code "60") (name "unconnected-(AT1-PB7_(PCINT15{slash}SCK)-Pad3)") (class "Default")
      (node (ref "AT1") (pin "3") (pinfunction "PB7_(PCINT15/SCK)_3") (pintype "passive"))
    )
    (net (code "61") (name "unconnected-(AT1-PC6_(TOSC1{slash}PCINT22)-Pad25)") (class "Default")
      (node (ref "AT1") (pin "25") (pinfunction "PC6_(TOSC1/PCINT22)_25") (pintype "passive"))
    )
    (net (code "62") (name "unconnected-(AT1-PC7_(TOSC2{slash}PCINT23)-Pad26)") (class "Default")
      (node (ref "AT1") (pin "26") (pinfunction "PC7_(TOSC2/PCINT23)_26") (pintype "passive"))
    )
    (net (code "63") (name "unconnected-(AT1-PD2_(PCINT26{slash}RXD1{slash}INT0)-Pad11)") (class "Default")
      (node (ref "AT1") (pin "11") (pinfunction "PD2_(PCINT26/RXD1/INT0)_11") (pintype "passive"))
    )
    (net (code "64") (name "unconnected-(AT1-PD3_(PCINT27{slash}TXD1{slash}INT1)-Pad12)") (class "Default")
      (node (ref "AT1") (pin "12") (pinfunction "PD3_(PCINT27/TXD1/INT1)_12") (pintype "passive"))
    )
    (net (code "65") (name "unconnected-(AT1-PD4_(PCINT28{slash}XCK1{slash}OC1B)-Pad13)") (class "Default")
      (node (ref "AT1") (pin "13") (pinfunction "PD4_(PCINT28/XCK1/OC1B)_13") (pintype "passive"))
    )
    (net (code "66") (name "unconnected-(AT1-PD5_(PCINT29{slash}OC1A)-Pad14)") (class "Default")
      (node (ref "AT1") (pin "14") (pinfunction "PD5_(PCINT29/OC1A)_14") (pintype "passive"))
    )
    (net (code "67") (name "unconnected-(AT1-PD6_(PCINT30{slash}OC2B{slash}ICP1)-Pad15)") (class "Default")
      (node (ref "AT1") (pin "15") (pinfunction "PD6_(PCINT30/OC2B/ICP1)_15") (pintype "passive"))
    )
    (net (code "68") (name "unconnected-(AT1-PD7_(PCINT31{slash}OC2A)-Pad16)") (class "Default")
      (node (ref "AT1") (pin "16") (pinfunction "PD7_(PCINT31/OC2A)_16") (pintype "passive"))
    )
    (net (code "69") (name "unconnected-(JT1-(TRST)-Pad8)") (class "Default")
      (node (ref "JT1") (pin "8") (pinfunction "(TRST)_8") (pintype "passive"))
    )
    (net (code "70") (name "unconnected-(JT1-NC-Pad7)") (class "Default")
      (node (ref "JT1") (pin "7") (pinfunction "NC_7") (pintype "passive"))
    )
    (net (code "71") (name "unconnected-(JT1-RST-Pad6)") (class "Default")
      (node (ref "JT1") (pin "6") (pinfunction "RST_6") (pintype "passive"))
    )
    (net (code "72") (name "unconnected-(U3-AUX_CL-Pad7)") (class "Default")
      (node (ref "U3") (pin "7") (pinfunction "AUX_CL_7") (pintype "passive"))
    )
    (net (code "73") (name "unconnected-(U3-AUX_DA-Pad6)") (class "Default")
      (node (ref "U3") (pin "6") (pinfunction "AUX_DA_6") (pintype "passive"))
    )
    (net (code "74") (name "unconnected-(U3-NC-Pad2)") (class "Default")
      (node (ref "U3") (pin "2") (pinfunction "NC_2") (pintype "passive"))
    )
    (net (code "75") (name "unconnected-(U3-NC-Pad3)") (class "Default")
      (node (ref "U3") (pin "3") (pinfunction "NC_3") (pintype "passive"))
    )
    (net (code "76") (name "unconnected-(U3-NC-Pad4)") (class "Default")
      (node (ref "U3") (pin "4") (pinfunction "NC_4") (pintype "passive"))
    )
    (net (code "77") (name "unconnected-(U3-NC-Pad5)") (class "Default")
      (node (ref "U3") (pin "5") (pinfunction "NC_5") (pintype "passive"))
    )
    (net (code "78") (name "unconnected-(U3-NC-Pad14)") (class "Default")
      (node (ref "U3") (pin "14") (pinfunction "NC_14") (pintype "passive"))
    )
    (net (code "79") (name "unconnected-(U3-NC-Pad15)") (class "Default")
      (node (ref "U3") (pin "15") (pinfunction "NC_15") (pintype "passive"))
    )
    (net (code "80") (name "unconnected-(U3-NC-Pad16)") (class "Default")
      (node (ref "U3") (pin "16") (pinfunction "NC_16") (pintype "passive"))
    )
    (net (code "81") (name "unconnected-(U3-NC-Pad17)") (class "Default")
      (node (ref "U3") (pin "17") (pinfunction "NC_17") (pintype "passive"))
    )
    (net (code "82") (name "unconnected-(U3-RESV-Pad19)") (class "Default")
      (node (ref "U3") (pin "19") (pinfunction "RESV_19") (pintype "passive"))
    )
    (net (code "83") (name "unconnected-(U3-RESV-Pad21)") (class "Default")
      (node (ref "U3") (pin "21") (pinfunction "RESV_21") (pintype "passive"))
    )
    (net (code "84") (name "unconnected-(U3-RESV-Pad22)") (class "Default")
      (node (ref "U3") (pin "22") (pinfunction "RESV_22") (pintype "passive"))
    )
    (net (code "85") (name "unconnected-(U4-3.3V-Pad10)") (class "Default")
      (node (ref "U4") (pin "10") (pinfunction "3.3V_10") (pintype "passive"))
    )
    (net (code "86") (name "unconnected-(U4-5V_OUT-Pad2)") (class "Default")
      (node (ref "U4") (pin "2") (pinfunction "5V_OUT_2") (pintype "passive"))
    )
    (net (code "87") (name "unconnected-(U4-IO2-Pad4)") (class "Default")
      (node (ref "U4") (pin "4") (pinfunction "IO2_4") (pintype "passive"))
    )
    (net (code "88") (name "unconnected-(U5-NC-Pad1)") (class "Default")
      (node (ref "U5") (pin "1") (pinfunction "NC_1") (pintype "passive"))
    )
    (net (code "89") (name "unconnected-(U5-NC-Pad5)") (class "Default")
      (node (ref "U5") (pin "5") (pinfunction "NC_5") (pintype "passive"))
    )
    (net (code "90") (name "unconnected-(U5-NC-Pad6)") (class "Default")
      (node (ref "U5") (pin "6") (pinfunction "NC_6") (pintype "passive"))
    )
    (net (code "91") (name "unconnected-(U5-NC-Pad7)") (class "Default")
      (node (ref "U5") (pin "7") (pinfunction "NC_7") (pintype "passive"))
    )
    (net (code "92") (name "unconnected-(U5-NC-Pad8)") (class "Default")
      (node (ref "U5") (pin "8") (pinfunction "NC_8") (pintype "passive"))
    )
    (net (code "93") (name "unconnected-(U5-NC-Pad14)") (class "Default")
      (node (ref "U5") (pin "14") (pinfunction "NC_14") (pintype "passive"))
    )
    (net (code "94") (name "unconnected-(USB1-Data+-Pad3)") (class "Default")
      (node (ref "USB1") (pin "3") (pinfunction "Data+_3") (pintype "passive"))
    )
    (net (code "95") (name "unconnected-(USB1-Data--Pad2)") (class "Default")
      (node (ref "USB1") (pin "2") (pinfunction "Data-_2") (pintype "passive"))
    )
    (net (code "96") (name "unconnected-(USB1-ID-Pad4)") (class "Default")
      (node (ref "USB1") (pin "4") (pinfunction "ID_4") (pintype "passive"))
    )
  )
)
